# EIB_A79024-001.net
KiCad netlist of a schematic drawn in EAGLE
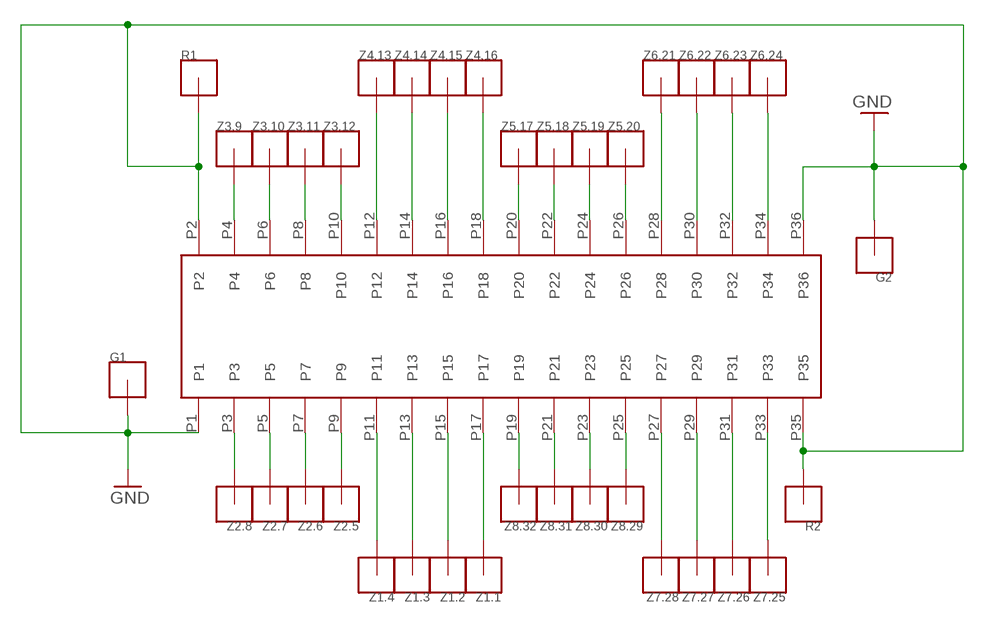
[diagram p0: schematic, sheet 1]

(export (version "E")
  (design (tool "Eeschema 10.0.6"))
  (components
    (comp (ref "A79024")
      (value "OMNETICS")
      (footprint "eagle-import:A79024")
      (libsource (lib "eagle-import") (part "OMNETICS"))
    )
    (comp (ref "G1")
      (value "S_P_HOLE")
      (footprint "eagle-import:S_P_HOLE")
      (libsource (lib "eagle-import") (part "S_P_HOLE"))
    )
    (comp (ref "G2")
      (value "S_P_HOLE")
      (footprint "eagle-import:S_P_HOLE")
      (libsource (lib "eagle-import") (part "S_P_HOLE"))
    )
    (comp (ref "R1")
      (value "S_P_HOLE")
      (footprint "eagle-import:S_P_HOLE")
      (libsource (lib "eagle-import") (part "S_P_HOLE"))
    )
    (comp (ref "R2")
      (value "S_P_HOLE")
      (footprint "eagle-import:S_P_HOLE")
      (libsource (lib "eagle-import") (part "S_P_HOLE"))
    )
    (comp (ref "Z1.1")
      (value "S_P_HOLE")
      (footprint "eagle-import:S_P_HOLE")
      (libsource (lib "eagle-import") (part "S_P_HOLE"))
    )
    (comp (ref "Z1.2")
      (value "S_P_HOLE")
      (footprint "eagle-import:S_P_HOLE")
      (libsource (lib "eagle-import") (part "S_P_HOLE"))
    )
    (comp (ref "Z1.3")
      (value "S_P_HOLE")
      (footprint "eagle-import:S_P_HOLE")
      (libsource (lib "eagle-import") (part "S_P_HOLE"))
    )
    (comp (ref "Z1.4")
      (value "S_P_HOLE")
      (footprint "eagle-import:S_P_HOLE")
      (libsource (lib "eagle-import") (part "S_P_HOLE"))
    )
    (comp (ref "Z2.5")
      (value "S_P_HOLE")
      (footprint "eagle-import:S_P_HOLE")
      (libsource (lib "eagle-import") (part "S_P_HOLE"))
    )
    (comp (ref "Z2.6")
      (value "S_P_HOLE")
      (footprint "eagle-import:S_P_HOLE")
      (libsource (lib "eagle-import") (part "S_P_HOLE"))
    )
    (comp (ref "Z2.7")
      (value "S_P_HOLE")
      (footprint "eagle-import:S_P_HOLE")
      (libsource (lib "eagle-import") (part "S_P_HOLE"))
    )
    (comp (ref "Z2.8")
      (value "S_P_HOLE")
      (footprint "eagle-import:S_P_HOLE")
      (libsource (lib "eagle-import") (part "S_P_HOLE"))
    )
    (comp (ref "Z3.9")
      (value "S_P_HOLE")
      (footprint "eagle-import:S_P_HOLE")
      (libsource (lib "eagle-import") (part "S_P_HOLE"))
    )
    (comp (ref "Z3.10")
      (value "S_P_HOLE")
      (footprint "eagle-import:S_P_HOLE")
      (libsource (lib "eagle-import") (part "S_P_HOLE"))
    )
    (comp (ref "Z3.11")
      (value "S_P_HOLE")
      (footprint "eagle-import:S_P_HOLE")
      (libsource (lib "eagle-import") (part "S_P_HOLE"))
    )
    (comp (ref "Z3.12")
      (value "S_P_HOLE")
      (footprint "eagle-import:S_P_HOLE")
      (libsource (lib "eagle-import") (part "S_P_HOLE"))
    )
    (comp (ref "Z4.13")
      (value "S_P_HOLE")
      (footprint "eagle-import:S_P_HOLE")
      (libsource (lib "eagle-import") (part "S_P_HOLE"))
    )
    (comp (ref "Z4.14")
      (value "S_P_HOLE")
      (footprint "eagle-import:S_P_HOLE")
      (libsource (lib "eagle-import") (part "S_P_HOLE"))
    )
    (comp (ref "Z4.15")
      (value "S_P_HOLE")
      (footprint "eagle-import:S_P_HOLE")
      (libsource (lib "eagle-import") (part "S_P_HOLE"))
    )
    (comp (ref "Z4.16")
      (value "S_P_HOLE")
      (footprint "eagle-import:S_P_HOLE")
      (libsource (lib "eagle-import") (part "S_P_HOLE"))
    )
    (comp (ref "Z5.17")
      (value "S_P_HOLE")
      (footprint "eagle-import:S_P_HOLE")
      (libsource (lib "eagle-import") (part "S_P_HOLE"))
    )
    (comp (ref "Z5.18")
      (value "S_P_HOLE")
      (footprint "eagle-import:S_P_HOLE")
      (libsource (lib "eagle-import") (part "S_P_HOLE"))
    )
    (comp (ref "Z5.19")
      (value "S_P_HOLE")
      (footprint "eagle-import:S_P_HOLE")
      (libsource (lib "eagle-import") (part "S_P_HOLE"))
    )
    (comp (ref "Z5.20")
      (value "S_P_HOLE")
      (footprint "eagle-import:S_P_HOLE")
      (libsource (lib "eagle-import") (part "S_P_HOLE"))
    )
    (comp (ref "Z6.21")
      (value "S_P_HOLE")
      (footprint "eagle-import:S_P_HOLE")
      (libsource (lib "eagle-import") (part "S_P_HOLE"))
    )
    (comp (ref "Z6.22")
      (value "S_P_HOLE")
      (footprint "eagle-import:S_P_HOLE")
      (libsource (lib "eagle-import") (part "S_P_HOLE"))
    )
    (comp (ref "Z6.23")
      (value "S_P_HOLE")
      (footprint "eagle-import:S_P_HOLE")
      (libsource (lib "eagle-import") (part "S_P_HOLE"))
    )
    (comp (ref "Z6.24")
      (value "S_P_HOLE")
      (footprint "eagle-import:S_P_HOLE")
      (libsource (lib "eagle-import") (part "S_P_HOLE"))
    )
    (comp (ref "Z7.25")
      (value "S_P_HOLE")
      (footprint "eagle-import:S_P_HOLE")
      (libsource (lib "eagle-import") (part "S_P_HOLE"))
    )
    (comp (ref "Z7.26")
      (value "S_P_HOLE")
      (footprint "eagle-import:S_P_HOLE")
      (libsource (lib "eagle-import") (part "S_P_HOLE"))
    )
    (comp (ref "Z7.27")
      (value "S_P_HOLE")
      (footprint "eagle-import:S_P_HOLE")
      (libsource (lib "eagle-import") (part "S_P_HOLE"))
    )
    (comp (ref "Z7.28")
      (value "S_P_HOLE")
      (footprint "eagle-import:S_P_HOLE")
      (libsource (lib "eagle-import") (part "S_P_HOLE"))
    )
    (comp (ref "Z8.29")
      (value "S_P_HOLE")
      (footprint "eagle-import:S_P_HOLE")
      (libsource (lib "eagle-import") (part "S_P_HOLE"))
    )
    (comp (ref "Z8.30")
      (value "S_P_HOLE")
      (footprint "eagle-import:S_P_HOLE")
      (libsource (lib "eagle-import") (part "S_P_HOLE"))
    )
    (comp (ref "Z8.31")
      (value "S_P_HOLE")
      (footprint "eagle-import:S_P_HOLE")
      (libsource (lib "eagle-import") (part "S_P_HOLE"))
    )
    (comp (ref "Z8.32")
      (value "S_P_HOLE")
      (footprint "eagle-import:S_P_HOLE")
      (libsource (lib "eagle-import") (part "S_P_HOLE"))
    )
  )
  (nets
    (net (code "1") (name "GND") (class "Default")
      (node (ref "A79024") (pin "P1") (pinfunction "P1_P1") (pintype "bidirectional"))
      (node (ref "A79024") (pin "P2") (pinfunction "P2_P2") (pintype "bidirectional"))
      (node (ref "A79024") (pin "P35") (pinfunction "P35_P35") (pintype "bidirectional"))
      (node (ref "A79024") (pin "P36") (pinfunction "P36_P36") (pintype "bidirectional"))
      (node (ref "G1") (pin "P1") (pinfunction "P1_P1") (pintype "bidirectional"))
      (node (ref "G2") (pin "P1") (pinfunction "P1_P1") (pintype "bidirectional"))
      (node (ref "R1") (pin "P1") (pinfunction "P1_P1") (pintype "bidirectional"))
      (node (ref "R2") (pin "P1") (pinfunction "P1_P1") (pintype "bidirectional"))
    )
    (net (code "2") (name "Net-(A79024-PadP3)") (class "Default")
      (node (ref "A79024") (pin "P3") (pinfunction "P3_P3") (pintype "bidirectional"))
      (node (ref "Z2.8") (pin "P1") (pinfunction "P1_P1") (pintype "bidirectional"))
    )
    (net (code "3") (name "Net-(A79024-PadP4)") (class "Default")
      (node (ref "A79024") (pin "P4") (pinfunction "P4_P4") (pintype "bidirectional"))
      (node (ref "Z3.9") (pin "P1") (pinfunction "P1_P1") (pintype "bidirectional"))
    )
    (net (code "4") (name "Net-(A79024-PadP5)") (class "Default")
      (node (ref "A79024") (pin "P5") (pinfunction "P5_P5") (pintype "bidirectional"))
      (node (ref "Z2.7") (pin "P1") (pinfunction "P1_P1") (pintype "bidirectional"))
    )
    (net (code "5") (name "Net-(A79024-PadP6)") (class "Default")
      (node (ref "A79024") (pin "P6") (pinfunction "P6_P6") (pintype "bidirectional"))
      (node (ref "Z3.10") (pin "P1") (pinfunction "P1_P1") (pintype "bidirectional"))
    )
    (net (code "6") (name "Net-(A79024-PadP7)") (class "Default")
      (node (ref "A79024") (pin "P7") (pinfunction "P7_P7") (pintype "bidirectional"))
      (node (ref "Z2.6") (pin "P1") (pinfunction "P1_P1") (pintype "bidirectional"))
    )
    (net (code "7") (name "Net-(A79024-PadP8)") (class "Default")
      (node (ref "A79024") (pin "P8") (pinfunction "P8_P8") (pintype "bidirectional"))
      (node (ref "Z3.11") (pin "P1") (pinfunction "P1_P1") (pintype "bidirectional"))
    )
    (net (code "8") (name "Net-(A79024-PadP9)") (class "Default")
      (node (ref "A79024") (pin "P9") (pinfunction "P9_P9") (pintype "bidirectional"))
      (node (ref "Z2.5") (pin "P1") (pinfunction "P1_P1") (pintype "bidirectional"))
    )
    (net (code "9") (name "Net-(A79024-PadP10)") (class "Default")
      (node (ref "A79024") (pin "P10") (pinfunction "P10_P10") (pintype "bidirectional"))
      (node (ref "Z3.12") (pin "P1") (pinfunction "P1_P1") (pintype "bidirectional"))
    )
    (net (code "10") (name "Net-(A79024-PadP11)") (class "Default")
      (node (ref "A79024") (pin "P11") (pinfunction "P11_P11") (pintype "bidirectional"))
      (node (ref "Z1.4") (pin "P1") (pinfunction "P1_P1") (pintype "bidirectional"))
    )
    (net (code "11") (name "Net-(A79024-PadP12)") (class "Default")
      (node (ref "A79024") (pin "P12") (pinfunction "P12_P12") (pintype "bidirectional"))
      (node (ref "Z4.13") (pin "P1") (pinfunction "P1_P1") (pintype "bidirectional"))
    )
    (net (code "12") (name "Net-(A79024-PadP13)") (class "Default")
      (node (ref "A79024") (pin "P13") (pinfunction "P13_P13") (pintype "bidirectional"))
      (node (ref "Z1.3") (pin "P1") (pinfunction "P1_P1") (pintype "bidirectional"))
    )
    (net (code "13") (name "Net-(A79024-PadP14)") (class "Default")
      (node (ref "A79024") (pin "P14") (pinfunction "P14_P14") (pintype "bidirectional"))
      (node (ref "Z4.14") (pin "P1") (pinfunction "P1_P1") (pintype "bidirectional"))
    )
    (net (code "14") (name "Net-(A79024-PadP15)") (class "Default")
      (node (ref "A79024") (pin "P15") (pinfunction "P15_P15") (pintype "bidirectional"))
      (node (ref "Z1.2") (pin "P1") (pinfunction "P1_P1") (pintype "bidirectional"))
    )
    (net (code "15") (name "Net-(A79024-PadP16)") (class "Default")
      (node (ref "A79024") (pin "P16") (pinfunction "P16_P16") (pintype "bidirectional"))
      (node (ref "Z4.15") (pin "P1") (pinfunction "P1_P1") (pintype "bidirectional"))
    )
    (net (code "16") (name "Net-(A79024-PadP17)") (class "Default")
      (node (ref "A79024") (pin "P17") (pinfunction "P17_P17") (pintype "bidirectional"))
      (node (ref "Z1.1") (pin "P1") (pinfunction "P1_P1") (pintype "bidirectional"))
    )
    (net (code "17") (name "Net-(A79024-PadP18)") (class "Default")
      (node (ref "A79024") (pin "P18") (pinfunction "P18_P18") (pintype "bidirectional"))
      (node (ref "Z4.16") (pin "P1") (pinfunction "P1_P1") (pintype "bidirectional"))
    )
    (net (code "18") (name "Net-(A79024-PadP19)") (class "Default")
      (node (ref "A79024") (pin "P19") (pinfunction "P19_P19") (pintype "bidirectional"))
      (node (ref "Z8.32") (pin "P1") (pinfunction "P1_P1") (pintype "bidirectional"))
    )
    (net (code "19") (name "Net-(A79024-PadP20)") (class "Default")
      (node (ref "A79024") (pin "P20") (pinfunction "P20_P20") (pintype "bidirectional"))
      (node (ref "Z5.17") (pin "P1") (pinfunction "P1_P1") (pintype "bidirectional"))
    )
    (net (code "20") (name "Net-(A79024-PadP21)") (class "Default")
      (node (ref "A79024") (pin "P21") (pinfunction "P21_P21") (pintype "bidirectional"))
      (node (ref "Z8.31") (pin "P1") (pinfunction "P1_P1") (pintype "bidirectional"))
    )
    (net (code "21") (name "Net-(A79024-PadP22)") (class "Default")
      (node (ref "A79024") (pin "P22") (pinfunction "P22_P22") (pintype "bidirectional"))
      (node (ref "Z5.18") (pin "P1") (pinfunction "P1_P1") (pintype "bidirectional"))
    )
    (net (code "22") (name "Net-(A79024-PadP23)") (class "Default")
      (node (ref "A79024") (pin "P23") (pinfunction "P23_P23") (pintype "bidirectional"))
      (node (ref "Z8.30") (pin "P1") (pinfunction "P1_P1") (pintype "bidirectional"))
    )
    (net (code "23") (name "Net-(A79024-PadP24)") (class "Default")
      (node (ref "A79024") (pin "P24") (pinfunction "P24_P24") (pintype "bidirectional"))
      (node (ref "Z5.19") (pin "P1") (pinfunction "P1_P1") (pintype "bidirectional"))
    )
    (net (code "24") (name "Net-(A79024-PadP25)") (class "Default")
      (node (ref "A79024") (pin "P25") (pinfunction "P25_P25") (pintype "bidirectional"))
      (node (ref "Z8.29") (pin "P1") (pinfunction "P1_P1") (pintype "bidirectional"))
    )
    (net (code "25") (name "Net-(A79024-PadP26)") (class "Default")
      (node (ref "A79024") (pin "P26") (pinfunction "P26_P26") (pintype "bidirectional"))
      (node (ref "Z5.20") (pin "P1") (pinfunction "P1_P1") (pintype "bidirectional"))
    )
    (net (code "26") (name "Net-(A79024-PadP27)") (class "Default")
      (node (ref "A79024") (pin "P27") (pinfunction "P27_P27") (pintype "bidirectional"))
      (node (ref "Z7.28") (pin "P1") (pinfunction "P1_P1") (pintype "bidirectional"))
    )
    (net (code "27") (name "Net-(A79024-PadP28)") (class "Default")
      (node (ref "A79024") (pin "P28") (pinfunction "P28_P28") (pintype "bidirectional"))
      (node (ref "Z6.21") (pin "P1") (pinfunction "P1_P1") (pintype "bidirectional"))
    )
    (net (code "28") (name "Net-(A79024-PadP29)") (class "Default")
      (node (ref "A79024") (pin "P29") (pinfunction "P29_P29") (pintype "bidirectional"))
      (node (ref "Z7.27") (pin "P1") (pinfunction "P1_P1") (pintype "bidirectional"))
    )
    (net (code "29") (name "Net-(A79024-PadP30)") (class "Default")
      (node (ref "A79024") (pin "P30") (pinfunction "P30_P30") (pintype "bidirectional"))
      (node (ref "Z6.22") (pin "P1") (pinfunction "P1_P1") (pintype "bidirectional"))
    )
    (net (code "30") (name "Net-(A79024-PadP31)") (class "Default")
      (node (ref "A79024") (pin "P31") (pinfunction "P31_P31") (pintype "bidirectional"))
      (node (ref "Z7.26") (pin "P1") (pinfunction "P1_P1") (pintype "bidirectional"))
    )
    (net (code "31") (name "Net-(A79024-PadP32)") (class "Default")
      (node (ref "A79024") (pin "P32") (pinfunction "P32_P32") (pintype "bidirectional"))
      (node (ref "Z6.23") (pin "P1") (pinfunction "P1_P1") (pintype "bidirectional"))
    )
    (net (code "32") (name "Net-(A79024-PadP33)") (class "Default")
      (node (ref "A79024") (pin "P33") (pinfunction "P33_P33") (pintype "bidirectional"))
      (node (ref "Z7.25") (pin "P1") (pinfunction "P1_P1") (pintype "bidirectional"))
    )
    (net (code "33") (name "Net-(A79024-PadP34)") (class "Default")
      (node (ref "A79024") (pin "P34") (pinfunction "P34_P34") (pintype "bidirectional"))
      (node (ref "Z6.24") (pin "P1") (pinfunction "P1_P1") (pintype "bidirectional"))
    )
  )
)
